# LCD.net
KiCad netlist of a schematic drawn in Altium Designer
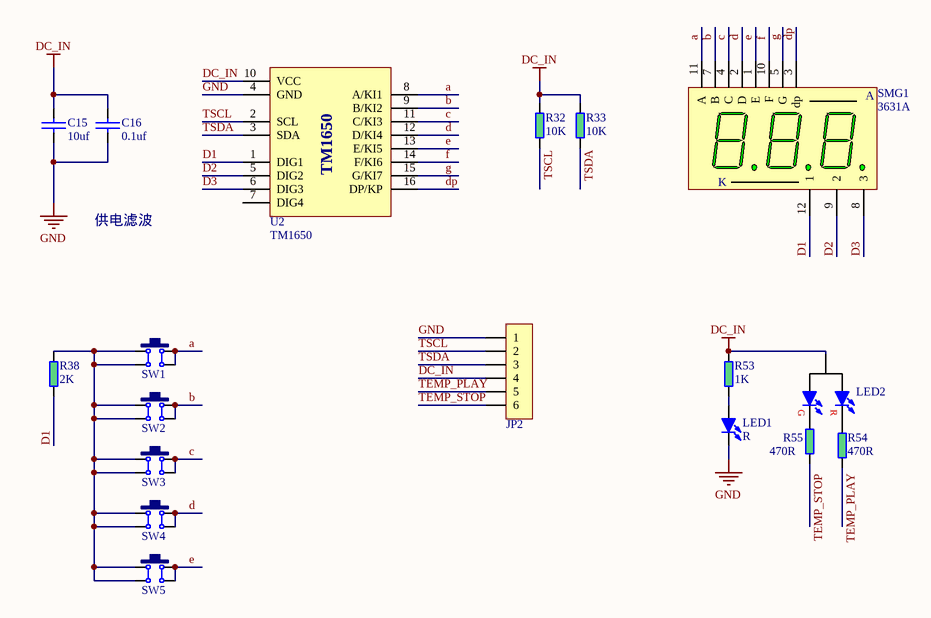
[diagram p0: LCD.SchDoc]

(export (version "E")
  (design (tool "Eeschema 10.0.6"))
  (components
    (comp (ref "C15")
      (value "10uf")
      (footprint "C 0603")
      (description "电容")
      (fields (field (name "Comment") "04.Cap"))
      (libsource (lib "电子元件") (part "04.Cap"))
    )
    (comp (ref "C16")
      (value "0.1uf")
      (footprint "C 0603")
      (description "电容")
      (fields (field (name "Comment") "04.Cap"))
      (libsource (lib "电子元件") (part "04.Cap"))
    )
    (comp (ref "JP2") (value "Pin06") (footprint "XH2.54 6P") (libsource (lib "接插件") (part "Pin06")))
    (comp (ref "LED1")
      (value "R")
      (footprint "LED 3mm R")
      (description "LED")
      (libsource (lib "电子元件") (part "15.Diode - LED"))
    )
    (comp (ref "LED2")
      (value "15.Diode - PLED - double")
      (footprint "LED 3mm R/G")
      (libsource (lib "电子元件") (part "15.Diode - PLED - double"))
    )
    (comp (ref "R32")
      (value "10K")
      (footprint "R 0603")
      (description "电阻")
      (libsource (lib "电子元件") (part "01.Res"))
    )
    (comp (ref "R33")
      (value "10K")
      (footprint "R 0603")
      (description "电阻")
      (libsource (lib "电子元件") (part "01.Res"))
    )
    (comp (ref "R38")
      (value "2K")
      (footprint "R 0603")
      (description "电阻")
      (libsource (lib "电子元件") (part "01.Res"))
    )
    (comp (ref "R53")
      (value "1K")
      (footprint "R 0603")
      (description "电阻")
      (libsource (lib "电子元件") (part "01.Res"))
    )
    (comp (ref "R54")
      (value "470R")
      (footprint "R 0603")
      (description "电阻")
      (libsource (lib "电子元件") (part "01.Res"))
    )
    (comp (ref "R55")
      (value "470R")
      (footprint "R 0603")
      (description "电阻")
      (libsource (lib "电子元件") (part "01.Res"))
    )
    (comp (ref "SMG1")
      (value "3631A")
      (footprint "SMG 0.36-3P")
      (description "0.36寸3位共阴数码管")
      (fields (field (name "版权归属") "源创客"))
      (libsource (lib "显示器件") (part "3631A"))
    )
    (comp (ref "SW1")
      (value "TSW DIP-6x6")
      (footprint "TSW DIP-6*6")
      (description "6x6轻触开关")
      (libsource (lib "按钮开关") (part "TSW DIP-6x6"))
    )
    (comp (ref "SW2")
      (value "TSW DIP-6x6")
      (footprint "TSW DIP-6*6")
      (description "6x6轻触开关")
      (libsource (lib "按钮开关") (part "TSW DIP-6x6"))
    )
    (comp (ref "SW3")
      (value "TSW DIP-6x6")
      (footprint "TSW DIP-6*6")
      (description "6x6轻触开关")
      (libsource (lib "按钮开关") (part "TSW DIP-6x6"))
    )
    (comp (ref "SW4")
      (value "TSW DIP-6x6")
      (footprint "TSW DIP-6*6")
      (description "6x6轻触开关")
      (libsource (lib "按钮开关") (part "TSW DIP-6x6"))
    )
    (comp (ref "SW5")
      (value "TSW DIP-6x6")
      (footprint "TSW DIP-6*6")
      (description "6x6轻触开关")
      (libsource (lib "按钮开关") (part "TSW DIP-6x6"))
    )
    (comp (ref "U2")
      (value "TM1650")
      (footprint "SOP16")
      (description "数码管驱动芯片")
      (libsource (lib "集成IC") (part "TM1650"))
    )
  )
  (nets
    (net (code "1") (name "/D1") (class "Default")
      (node (ref "R38") (pin "1") (pinfunction "1_1") (pintype "passive"))
      (node (ref "SMG1") (pin "12") (pinfunction "1_12") (pintype "passive"))
      (node (ref "U2") (pin "1") (pinfunction "DIG1_1") (pintype "passive"))
    )
    (net (code "2") (name "/D2") (class "Default")
      (node (ref "SMG1") (pin "9") (pinfunction "2_9") (pintype "passive"))
      (node (ref "U2") (pin "5") (pinfunction "DIG2_5") (pintype "passive"))
    )
    (net (code "3") (name "/D3") (class "Default")
      (node (ref "SMG1") (pin "8") (pinfunction "3_8") (pintype "passive"))
      (node (ref "U2") (pin "6") (pinfunction "DIG3_6") (pintype "passive"))
    )
    (net (code "4") (name "/TEMP_PLAY") (class "Default")
      (node (ref "JP2") (pin "5") (pinfunction "5_5") (pintype "passive"))
      (node (ref "R54") (pin "1") (pinfunction "1_1") (pintype "passive"))
    )
    (net (code "5") (name "/TEMP_STOP") (class "Default")
      (node (ref "JP2") (pin "6") (pinfunction "6_6") (pintype "passive"))
      (node (ref "R55") (pin "1") (pinfunction "1_1") (pintype "passive"))
    )
    (net (code "6") (name "/TSCL") (class "Default")
      (node (ref "JP2") (pin "2") (pinfunction "2_2") (pintype "passive"))
      (node (ref "R32") (pin "1") (pinfunction "1_1") (pintype "passive"))
      (node (ref "U2") (pin "2") (pinfunction "SCL_2") (pintype "passive"))
    )
    (net (code "7") (name "/TSDA") (class "Default")
      (node (ref "JP2") (pin "3") (pinfunction "3_3") (pintype "passive"))
      (node (ref "R33") (pin "1") (pinfunction "1_1") (pintype "passive"))
      (node (ref "U2") (pin "3") (pinfunction "SDA_3") (pintype "passive"))
    )
    (net (code "8") (name "/a") (class "Default")
      (node (ref "SMG1") (pin "11") (pinfunction "A_11") (pintype "passive"))
      (node (ref "SW1") (pin "C") (pinfunction "C_C") (pintype "passive"))
      (node (ref "SW1") (pin "D") (pinfunction "D_D") (pintype "passive"))
      (node (ref "U2") (pin "8") (pinfunction "A/KI1_8") (pintype "passive"))
    )
    (net (code "9") (name "/b") (class "Default")
      (node (ref "SMG1") (pin "7") (pinfunction "B_7") (pintype "passive"))
      (node (ref "SW2") (pin "C") (pinfunction "C_C") (pintype "passive"))
      (node (ref "SW2") (pin "D") (pinfunction "D_D") (pintype "passive"))
      (node (ref "U2") (pin "9") (pinfunction "B/KI2_9") (pintype "passive"))
    )
    (net (code "10") (name "/c") (class "Default")
      (node (ref "SMG1") (pin "4") (pinfunction "C_4") (pintype "passive"))
      (node (ref "SW3") (pin "C") (pinfunction "C_C") (pintype "passive"))
      (node (ref "SW3") (pin "D") (pinfunction "D_D") (pintype "passive"))
      (node (ref "U2") (pin "11") (pinfunction "C/KI3_11") (pintype "passive"))
    )
    (net (code "11") (name "/d") (class "Default")
      (node (ref "SMG1") (pin "2") (pinfunction "D_2") (pintype "passive"))
      (node (ref "SW4") (pin "C") (pinfunction "C_C") (pintype "passive"))
      (node (ref "SW4") (pin "D") (pinfunction "D_D") (pintype "passive"))
      (node (ref "U2") (pin "12") (pinfunction "D/KI4_12") (pintype "passive"))
    )
    (net (code "12") (name "/dp") (class "Default")
      (node (ref "SMG1") (pin "3") (pinfunction "dp_3") (pintype "passive"))
      (node (ref "U2") (pin "16") (pinfunction "DP/KP_16") (pintype "passive"))
    )
    (net (code "13") (name "/e") (class "Default")
      (node (ref "SMG1") (pin "1") (pinfunction "E_1") (pintype "passive"))
      (node (ref "SW5") (pin "C") (pinfunction "C_C") (pintype "passive"))
      (node (ref "SW5") (pin "D") (pinfunction "D_D") (pintype "passive"))
      (node (ref "U2") (pin "13") (pinfunction "E/KI5_13") (pintype "passive"))
    )
    (net (code "14") (name "/f") (class "Default")
      (node (ref "SMG1") (pin "10") (pinfunction "F_10") (pintype "passive"))
      (node (ref "U2") (pin "14") (pinfunction "F/KI6_14") (pintype "passive"))
    )
    (net (code "15") (name "/g") (class "Default")
      (node (ref "SMG1") (pin "5") (pinfunction "G_5") (pintype "passive"))
      (node (ref "U2") (pin "15") (pinfunction "G/KI7_15") (pintype "passive"))
    )
    (net (code "16") (name "DC_IN") (class "Default")
      (node (ref "C15") (pin "1") (pinfunction "1_1") (pintype "passive"))
      (node (ref "C16") (pin "1") (pinfunction "1_1") (pintype "passive"))
      (node (ref "JP2") (pin "4") (pinfunction "4_4") (pintype "passive"))
      (node (ref "LED2") (pin "A") (pinfunction "A_A") (pintype "passive"))
      (node (ref "R32") (pin "2") (pinfunction "2_2") (pintype "passive"))
      (node (ref "R33") (pin "2") (pinfunction "2_2") (pintype "passive"))
      (node (ref "R53") (pin "2") (pinfunction "2_2") (pintype "passive"))
      (node (ref "U2") (pin "10") (pinfunction "VCC_10") (pintype "passive"))
    )
    (net (code "17") (name "GND") (class "Default")
      (node (ref "C15") (pin "2") (pinfunction "2_2") (pintype "passive"))
      (node (ref "C16") (pin "2") (pinfunction "2_2") (pintype "passive"))
      (node (ref "JP2") (pin "1") (pinfunction "1_1") (pintype "passive"))
      (node (ref "LED1") (pin "K") (pinfunction "K_K") (pintype "passive"))
      (node (ref "U2") (pin "4") (pinfunction "GND_4") (pintype "passive"))
    )
    (net (code "18") (name "Net-(LED1-PadA)") (class "Default")
      (node (ref "LED1") (pin "A") (pinfunction "A_A") (pintype "passive"))
      (node (ref "R53") (pin "1") (pinfunction "1_1") (pintype "passive"))
    )
    (net (code "19") (name "Net-(LED2-PadG)") (class "Default")
      (node (ref "LED2") (pin "G") (pinfunction "G_G") (pintype "passive"))
      (node (ref "R55") (pin "2") (pinfunction "2_2") (pintype "passive"))
    )
    (net (code "20") (name "Net-(LED2-PadR)") (class "Default")
      (node (ref "LED2") (pin "R") (pinfunction "R_R") (pintype "passive"))
      (node (ref "R54") (pin "2") (pinfunction "2_2") (pintype "passive"))
    )
    (net (code "21") (name "Net-(R38-Pad2)") (class "Default")
      (node (ref "R38") (pin "2") (pinfunction "2_2") (pintype "passive"))
      (node (ref "SW1") (pin "A") (pinfunction "A_A") (pintype "passive"))
      (node (ref "SW1") (pin "B") (pinfunction "B_B") (pintype "passive"))
      (node (ref "SW2") (pin "A") (pinfunction "A_A") (pintype "passive"))
      (node (ref "SW2") (pin "B") (pinfunction "B_B") (pintype "passive"))
      (node (ref "SW3") (pin "A") (pinfunction "A_A") (pintype "passive"))
      (node (ref "SW3") (pin "B") (pinfunction "B_B") (pintype "passive"))
      (node (ref "SW4") (pin "A") (pinfunction "A_A") (pintype "passive"))
      (node (ref "SW4") (pin "B") (pinfunction "B_B") (pintype "passive"))
      (node (ref "SW5") (pin "A") (pinfunction "A_A") (pintype "passive"))
      (node (ref "SW5") (pin "B") (pinfunction "B_B") (pintype "passive"))
    )
    (net (code "22") (name "unconnected-(U2-DIG4-Pad7)") (class "Default")
      (node (ref "U2") (pin "7") (pinfunction "DIG4_7") (pintype "passive"))
    )
  )
)
